# SAMV71_Xplained_Ultra_Shield_Connectors.net
KiCad netlist of a schematic drawn in Altium Designer
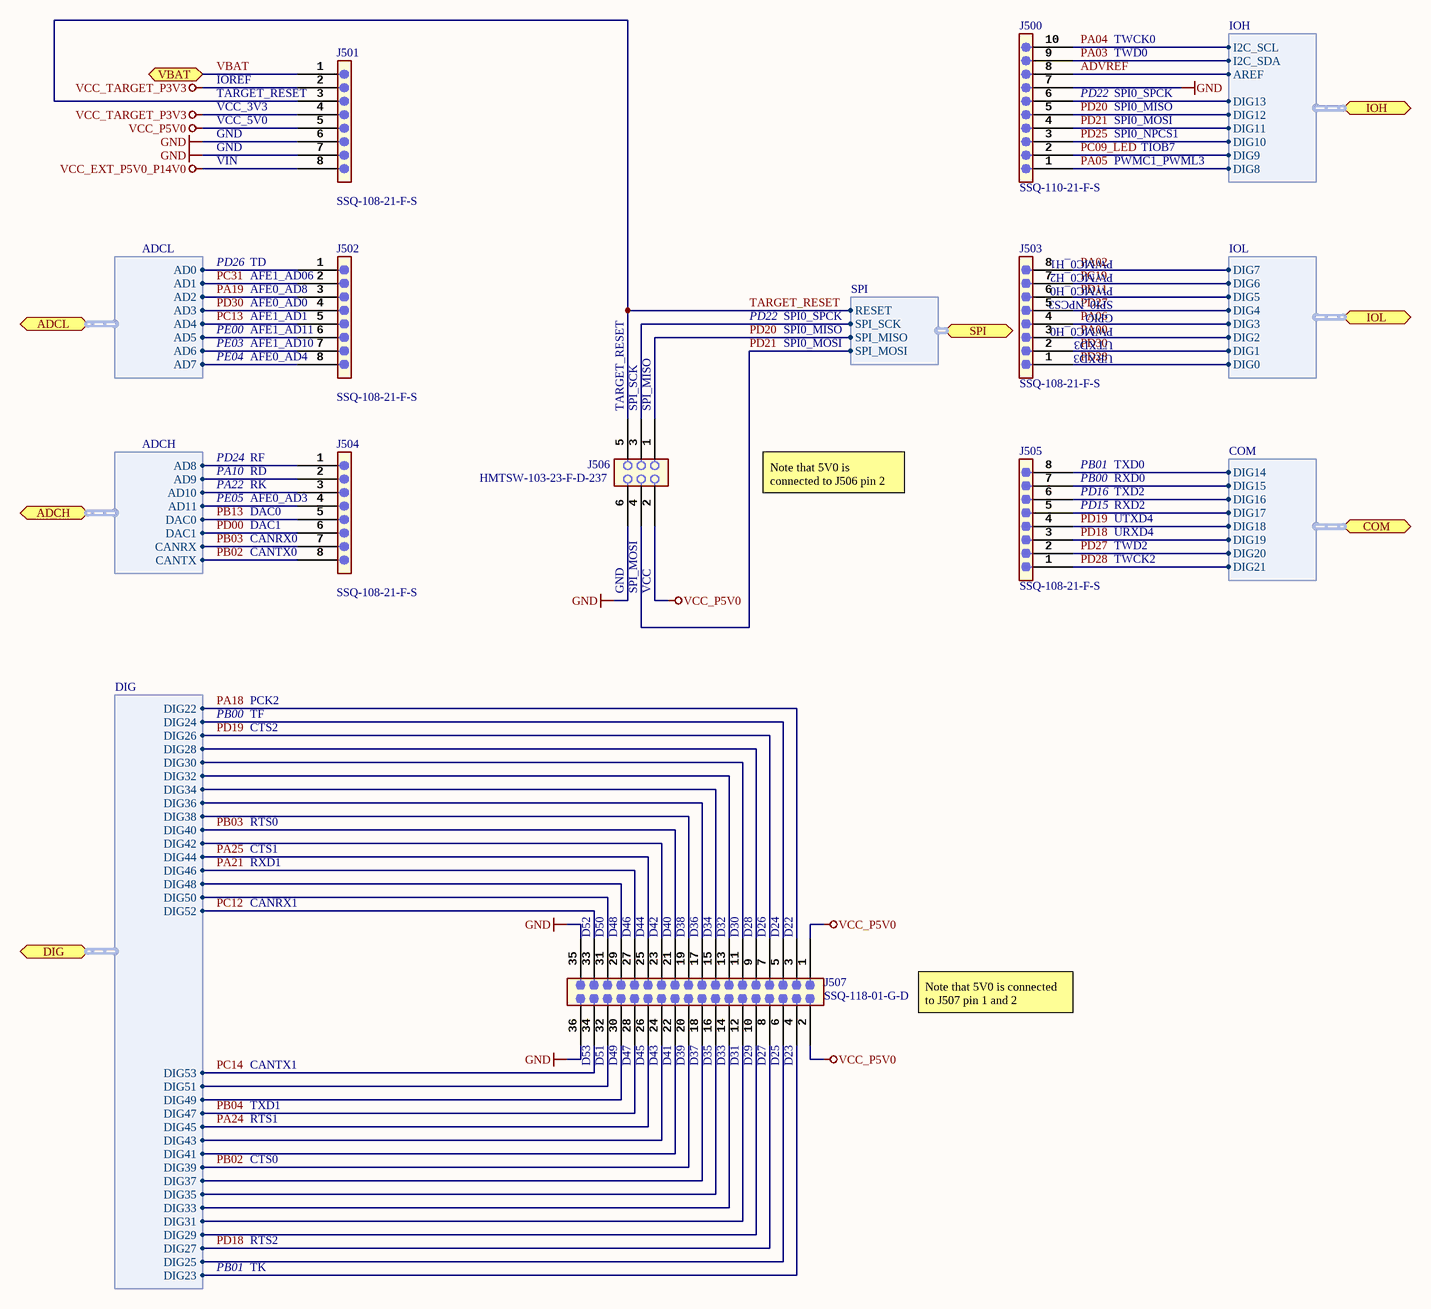
[diagram p0: SAMV71_Xplained_Ultra_Shield_Connectors.SchDoc]

(export (version "E")
  (design (tool "Eeschema 10.0.6"))
  (components
    (comp (ref "J500")
      (value "SSQ-110-21-F-S")
      (footprint "AP8-00822")
      (description "1x10 receptacle pin header, low insertion force, 2.54mm pitch THM, Pin in Paste")
      (fields (field (name "MANUFACTURER") "SAMTEC"))
      (libsource (lib "AltiumDbLib") (part "HEADER 1x10 FEMALE"))
    )
    (comp (ref "J501")
      (value "SSQ-108-21-F-S")
      (footprint "AP8-00823")
      (description "1x8 receptacle pin header, low insertion force, 2.54mm pitch THM, Pin in Paste")
      (fields (field (name "MANUFACTURER") "SAMTEC"))
      (libsource (lib "AltiumDbLib") (part "HEADER 1x8 FEMALE"))
    )
    (comp (ref "J502")
      (value "SSQ-108-21-F-S")
      (footprint "AP8-00823")
      (description "1x8 receptacle pin header, low insertion force, 2.54mm pitch THM, Pin in Paste")
      (fields (field (name "MANUFACTURER") "SAMTEC"))
      (libsource (lib "AltiumDbLib") (part "HEADER 1x8 FEMALE"))
    )
    (comp (ref "J503")
      (value "SSQ-108-21-F-S")
      (footprint "AP8-00823")
      (description "1x8 receptacle pin header, low insertion force, 2.54mm pitch THM, Pin in Paste")
      (fields (field (name "MANUFACTURER") "SAMTEC"))
      (libsource (lib "") (part "HEADER 1x8 FEMALE_1"))
    )
    (comp (ref "J504")
      (value "SSQ-108-21-F-S")
      (footprint "AP8-00823")
      (description "1x8 receptacle pin header, low insertion force, 2.54mm pitch THM, Pin in Paste")
      (fields (field (name "MANUFACTURER") "SAMTEC"))
      (libsource (lib "AltiumDbLib") (part "HEADER 1x8 FEMALE"))
    )
    (comp (ref "J505")
      (value "SSQ-108-21-F-S")
      (footprint "AP8-00823")
      (description "1x8 receptacle pin header, low insertion force, 2.54mm pitch THM, Pin in Paste")
      (fields (field (name "MANUFACTURER") "SAMTEC"))
      (libsource (lib "") (part "HEADER 1x8 FEMALE_1"))
    )
    (comp (ref "J506")
      (value "HMTSW-103-23-F-D-237")
      (footprint "AP8-00182")
      (description "2x3 pin header, 2.54mm pitch, Pin-in-Paste THM")
      (fields (field (name "MANUFACTURER") "SAMTEC"))
      (libsource (lib "AltiumDbLib") (part "HEADER 2x3"))
    )
    (comp (ref "J507")
      (value "SSQ-118-01-G-D")
      (footprint "AP8-00259")
      (description "2x18 female pin header, 2.54mm pitch, THM")
      (fields (field (name "MANUFACTURER") "SAMTEC"))
      (libsource (lib "AltiumDbLib") (part "HEADER 2x18 FEMALE"))
    )
  )
  (nets
    (net (code "8") (name "/AD0") (class "Default")
      (node (ref "J502") (pin "1") (pinfunction "1_1") (pintype "passive"))
    )
    (net (code "9") (name "/AD5") (class "Default")
      (node (ref "J502") (pin "6") (pinfunction "6_6") (pintype "passive"))
    )
    (net (code "10") (name "/AD6") (class "Default")
      (node (ref "J502") (pin "7") (pinfunction "7_7") (pintype "passive"))
    )
    (net (code "11") (name "/AD7") (class "Default")
      (node (ref "J502") (pin "8") (pinfunction "8_8") (pintype "passive"))
    )
    (net (code "12") (name "/AD8") (class "Default")
      (node (ref "J504") (pin "1") (pinfunction "1_1") (pintype "passive"))
    )
    (net (code "13") (name "/AD9") (class "Default")
      (node (ref "J504") (pin "2") (pinfunction "2_2") (pintype "passive"))
    )
    (net (code "14") (name "/AD10") (class "Default")
      (node (ref "J504") (pin "3") (pinfunction "3_3") (pintype "passive"))
    )
    (net (code "15") (name "/AD11") (class "Default")
      (node (ref "J504") (pin "4") (pinfunction "4_4") (pintype "passive"))
    )
    (net (code "16") (name "/ADVREF") (class "Default")
      (node (ref "J500") (pin "8") (pinfunction "8_8") (pintype "passive"))
    )
    (net (code "17") (name "/DIG13") (class "Default")
      (node (ref "J500") (pin "6") (pinfunction "6_6") (pintype "passive"))
    )
    (net (code "18") (name "/DIG14") (class "Default")
      (node (ref "J505") (pin "8") (pinfunction "8_8") (pintype "passive"))
    )
    (net (code "19") (name "/DIG15") (class "Default")
      (node (ref "J505") (pin "7") (pinfunction "7_7") (pintype "passive"))
    )
    (net (code "20") (name "/DIG16") (class "Default")
      (node (ref "J505") (pin "6") (pinfunction "6_6") (pintype "passive"))
    )
    (net (code "21") (name "/DIG17") (class "Default")
      (node (ref "J505") (pin "5") (pinfunction "5_5") (pintype "passive"))
    )
    (net (code "22") (name "/DIG23") (class "Default")
      (node (ref "J507") (pin "4") (pinfunction "4_4") (pintype "passive"))
    )
    (net (code "23") (name "/DIG24") (class "Default")
      (node (ref "J507") (pin "5") (pinfunction "5_5") (pintype "passive"))
    )
    (net (code "24") (name "/DIG25") (class "Default")
      (node (ref "J507") (pin "6") (pinfunction "6_6") (pintype "passive"))
    )
    (net (code "25") (name "/DIG28") (class "Default")
      (node (ref "J507") (pin "9") (pinfunction "9_9") (pintype "passive"))
    )
    (net (code "26") (name "/DIG29") (class "Default")
      (node (ref "J507") (pin "10") (pinfunction "10_10") (pintype "passive"))
    )
    (net (code "27") (name "/DIG30") (class "Default")
      (node (ref "J507") (pin "11") (pinfunction "11_11") (pintype "passive"))
    )
    (net (code "28") (name "/DIG31") (class "Default")
      (node (ref "J507") (pin "12") (pinfunction "12_12") (pintype "passive"))
    )
    (net (code "29") (name "/DIG32") (class "Default")
      (node (ref "J507") (pin "13") (pinfunction "13_13") (pintype "passive"))
    )
    (net (code "30") (name "/DIG33") (class "Default")
      (node (ref "J507") (pin "14") (pinfunction "14_14") (pintype "passive"))
    )
    (net (code "31") (name "/DIG34") (class "Default")
      (node (ref "J507") (pin "15") (pinfunction "15_15") (pintype "passive"))
    )
    (net (code "32") (name "/DIG35") (class "Default")
      (node (ref "J507") (pin "16") (pinfunction "16_16") (pintype "passive"))
    )
    (net (code "33") (name "/DIG36") (class "Default")
      (node (ref "J507") (pin "17") (pinfunction "17_17") (pintype "passive"))
    )
    (net (code "34") (name "/DIG37") (class "Default")
      (node (ref "J507") (pin "18") (pinfunction "18_18") (pintype "passive"))
    )
    (net (code "35") (name "/DIG38") (class "Default")
      (node (ref "J507") (pin "19") (pinfunction "19_19") (pintype "passive"))
    )
    (net (code "36") (name "/DIG41") (class "Default")
      (node (ref "J507") (pin "22") (pinfunction "22_22") (pintype "passive"))
    )
    (net (code "37") (name "/DIG42") (class "Default")
      (node (ref "J507") (pin "23") (pinfunction "23_23") (pintype "passive"))
    )
    (net (code "38") (name "/DIG43") (class "Default")
      (node (ref "J507") (pin "24") (pinfunction "24_24") (pintype "passive"))
    )
    (net (code "39") (name "/DIG48") (class "Default")
      (node (ref "J507") (pin "29") (pinfunction "29_29") (pintype "passive"))
    )
    (net (code "40") (name "/DIG49") (class "Default")
      (node (ref "J507") (pin "30") (pinfunction "30_30") (pintype "passive"))
    )
    (net (code "41") (name "/DIG50") (class "Default")
      (node (ref "J507") (pin "31") (pinfunction "31_31") (pintype "passive"))
    )
    (net (code "42") (name "/DIG51") (class "Default")
      (node (ref "J507") (pin "32") (pinfunction "32_32") (pintype "passive"))
    )
    (net (code "43") (name "/PA00") (class "Default")
      (node (ref "J503") (pin "3") (pinfunction "3_3") (pintype "passive"))
    )
    (net (code "44") (name "/PA02") (class "Default")
      (node (ref "J503") (pin "8") (pinfunction "8_8") (pintype "passive"))
    )
    (net (code "45") (name "/PA03") (class "Default")
      (node (ref "J500") (pin "9") (pinfunction "9_9") (pintype "passive"))
    )
    (net (code "46") (name "/PA04") (class "Default")
      (node (ref "J500") (pin "10") (pinfunction "10_10") (pintype "passive"))
    )
    (net (code "47") (name "/PA05") (class "Default")
      (node (ref "J500") (pin "1") (pinfunction "1_1") (pintype "passive"))
    )
    (net (code "48") (name "/PA06") (class "Default")
      (node (ref "J503") (pin "4") (pinfunction "4_4") (pintype "passive"))
    )
    (net (code "49") (name "/PA18") (class "Default")
      (node (ref "J507") (pin "3") (pinfunction "3_3") (pintype "passive"))
    )
    (net (code "50") (name "/PA19") (class "Default")
      (node (ref "J502") (pin "3") (pinfunction "3_3") (pintype "passive"))
    )
    (net (code "51") (name "/PA21") (class "Default")
      (node (ref "J507") (pin "27") (pinfunction "27_27") (pintype "passive"))
    )
    (net (code "52") (name "/PA24") (class "Default")
      (node (ref "J507") (pin "26") (pinfunction "26_26") (pintype "passive"))
    )
    (net (code "53") (name "/PA25") (class "Default")
      (node (ref "J507") (pin "25") (pinfunction "25_25") (pintype "passive"))
    )
    (net (code "54") (name "/PB02") (class "Default")
      (node (ref "J504") (pin "8") (pinfunction "8_8") (pintype "passive"))
      (node (ref "J507") (pin "20") (pinfunction "20_20") (pintype "passive"))
    )
    (net (code "55") (name "/PB03") (class "Default")
      (node (ref "J504") (pin "7") (pinfunction "7_7") (pintype "passive"))
      (node (ref "J507") (pin "21") (pinfunction "21_21") (pintype "passive"))
    )
    (net (code "56") (name "/PB04") (class "Default")
      (node (ref "J507") (pin "28") (pinfunction "28_28") (pintype "passive"))
    )
    (net (code "57") (name "/PB13") (class "Default")
      (node (ref "J504") (pin "5") (pinfunction "5_5") (pintype "passive"))
    )
    (net (code "58") (name "/PC09_LED") (class "Default")
      (node (ref "J500") (pin "2") (pinfunction "2_2") (pintype "passive"))
    )
    (net (code "59") (name "/PC12") (class "Default")
      (node (ref "J507") (pin "33") (pinfunction "33_33") (pintype "passive"))
    )
    (net (code "60") (name "/PC13") (class "Default")
      (node (ref "J502") (pin "5") (pinfunction "5_5") (pintype "passive"))
    )
    (net (code "61") (name "/PC14") (class "Default")
      (node (ref "J507") (pin "34") (pinfunction "34_34") (pintype "passive"))
    )
    (net (code "62") (name "/PC19") (class "Default")
      (node (ref "J503") (pin "7") (pinfunction "7_7") (pintype "passive"))
    )
    (net (code "63") (name "/PC31") (class "Default")
      (node (ref "J502") (pin "2") (pinfunction "2_2") (pintype "passive"))
    )
    (net (code "64") (name "/PD00") (class "Default")
      (node (ref "J504") (pin "6") (pinfunction "6_6") (pintype "passive"))
    )
    (net (code "65") (name "/PD11") (class "Default")
      (node (ref "J503") (pin "6") (pinfunction "6_6") (pintype "passive"))
    )
    (net (code "66") (name "/PD18") (class "Default")
      (node (ref "J505") (pin "3") (pinfunction "3_3") (pintype "passive"))
      (node (ref "J507") (pin "8") (pinfunction "8_8") (pintype "passive"))
    )
    (net (code "67") (name "/PD19") (class "Default")
      (node (ref "J505") (pin "4") (pinfunction "4_4") (pintype "passive"))
      (node (ref "J507") (pin "7") (pinfunction "7_7") (pintype "passive"))
    )
    (net (code "68") (name "/PD20") (class "Default")
      (node (ref "J500") (pin "5") (pinfunction "5_5") (pintype "passive"))
      (node (ref "J506") (pin "1") (pinfunction "1_1") (pintype "passive"))
    )
    (net (code "69") (name "/PD21") (class "Default")
      (node (ref "J500") (pin "4") (pinfunction "4_4") (pintype "passive"))
      (node (ref "J506") (pin "4") (pinfunction "4_4") (pintype "passive"))
    )
    (net (code "70") (name "/PD25") (class "Default")
      (node (ref "J500") (pin "3") (pinfunction "3_3") (pintype "passive"))
    )
    (net (code "71") (name "/PD27") (class "Default")
      (node (ref "J503") (pin "5") (pinfunction "5_5") (pintype "passive"))
      (node (ref "J505") (pin "2") (pinfunction "2_2") (pintype "passive"))
    )
    (net (code "72") (name "/PD28") (class "Default")
      (node (ref "J503") (pin "1") (pinfunction "1_1") (pintype "passive"))
      (node (ref "J505") (pin "1") (pinfunction "1_1") (pintype "passive"))
    )
    (net (code "73") (name "/PD30") (class "Default")
      (node (ref "J502") (pin "4") (pinfunction "4_4") (pintype "passive"))
      (node (ref "J503") (pin "2") (pinfunction "2_2") (pintype "passive"))
    )
    (net (code "74") (name "/SPI_SCK") (class "Default")
      (node (ref "J506") (pin "3") (pinfunction "3_3") (pintype "passive"))
    )
    (net (code "75") (name "/TARGET_RESET") (class "Default")
      (node (ref "J501") (pin "3") (pinfunction "3_3") (pintype "passive"))
      (node (ref "J506") (pin "5") (pinfunction "5_5") (pintype "passive"))
    )
    (net (code "76") (name "/VBAT") (class "Default")
      (node (ref "J501") (pin "1") (pinfunction "1_1") (pintype "passive"))
    )
    (net (code "84") (name "GND") (class "Default")
      (node (ref "J500") (pin "7") (pinfunction "7_7") (pintype "passive"))
      (node (ref "J501") (pin "6") (pinfunction "6_6") (pintype "passive"))
      (node (ref "J501") (pin "7") (pinfunction "7_7") (pintype "passive"))
      (node (ref "J506") (pin "6") (pinfunction "6_6") (pintype "passive"))
      (node (ref "J507") (pin "35") (pinfunction "35_35") (pintype "passive"))
      (node (ref "J507") (pin "36") (pinfunction "36_36") (pintype "passive"))
    )
    (net (code "85") (name "VCC_EXT_P5V0_P14V0") (class "Default")
      (node (ref "J501") (pin "8") (pinfunction "8_8") (pintype "passive"))
    )
    (net (code "86") (name "VCC_P5V0") (class "Default")
      (node (ref "J501") (pin "5") (pinfunction "5_5") (pintype "passive"))
      (node (ref "J506") (pin "2") (pinfunction "2_2") (pintype "passive"))
      (node (ref "J507") (pin "1") (pinfunction "1_1") (pintype "passive"))
      (node (ref "J507") (pin "2") (pinfunction "2_2") (pintype "passive"))
    )
    (net (code "87") (name "VCC_TARGET_P3V3") (class "Default")
      (node (ref "J501") (pin "2") (pinfunction "2_2") (pintype "passive"))
      (node (ref "J501") (pin "4") (pinfunction "4_4") (pintype "passive"))
    )
  )
)
